# Bench.net
KiCad netlist of a schematic drawn in EAGLE
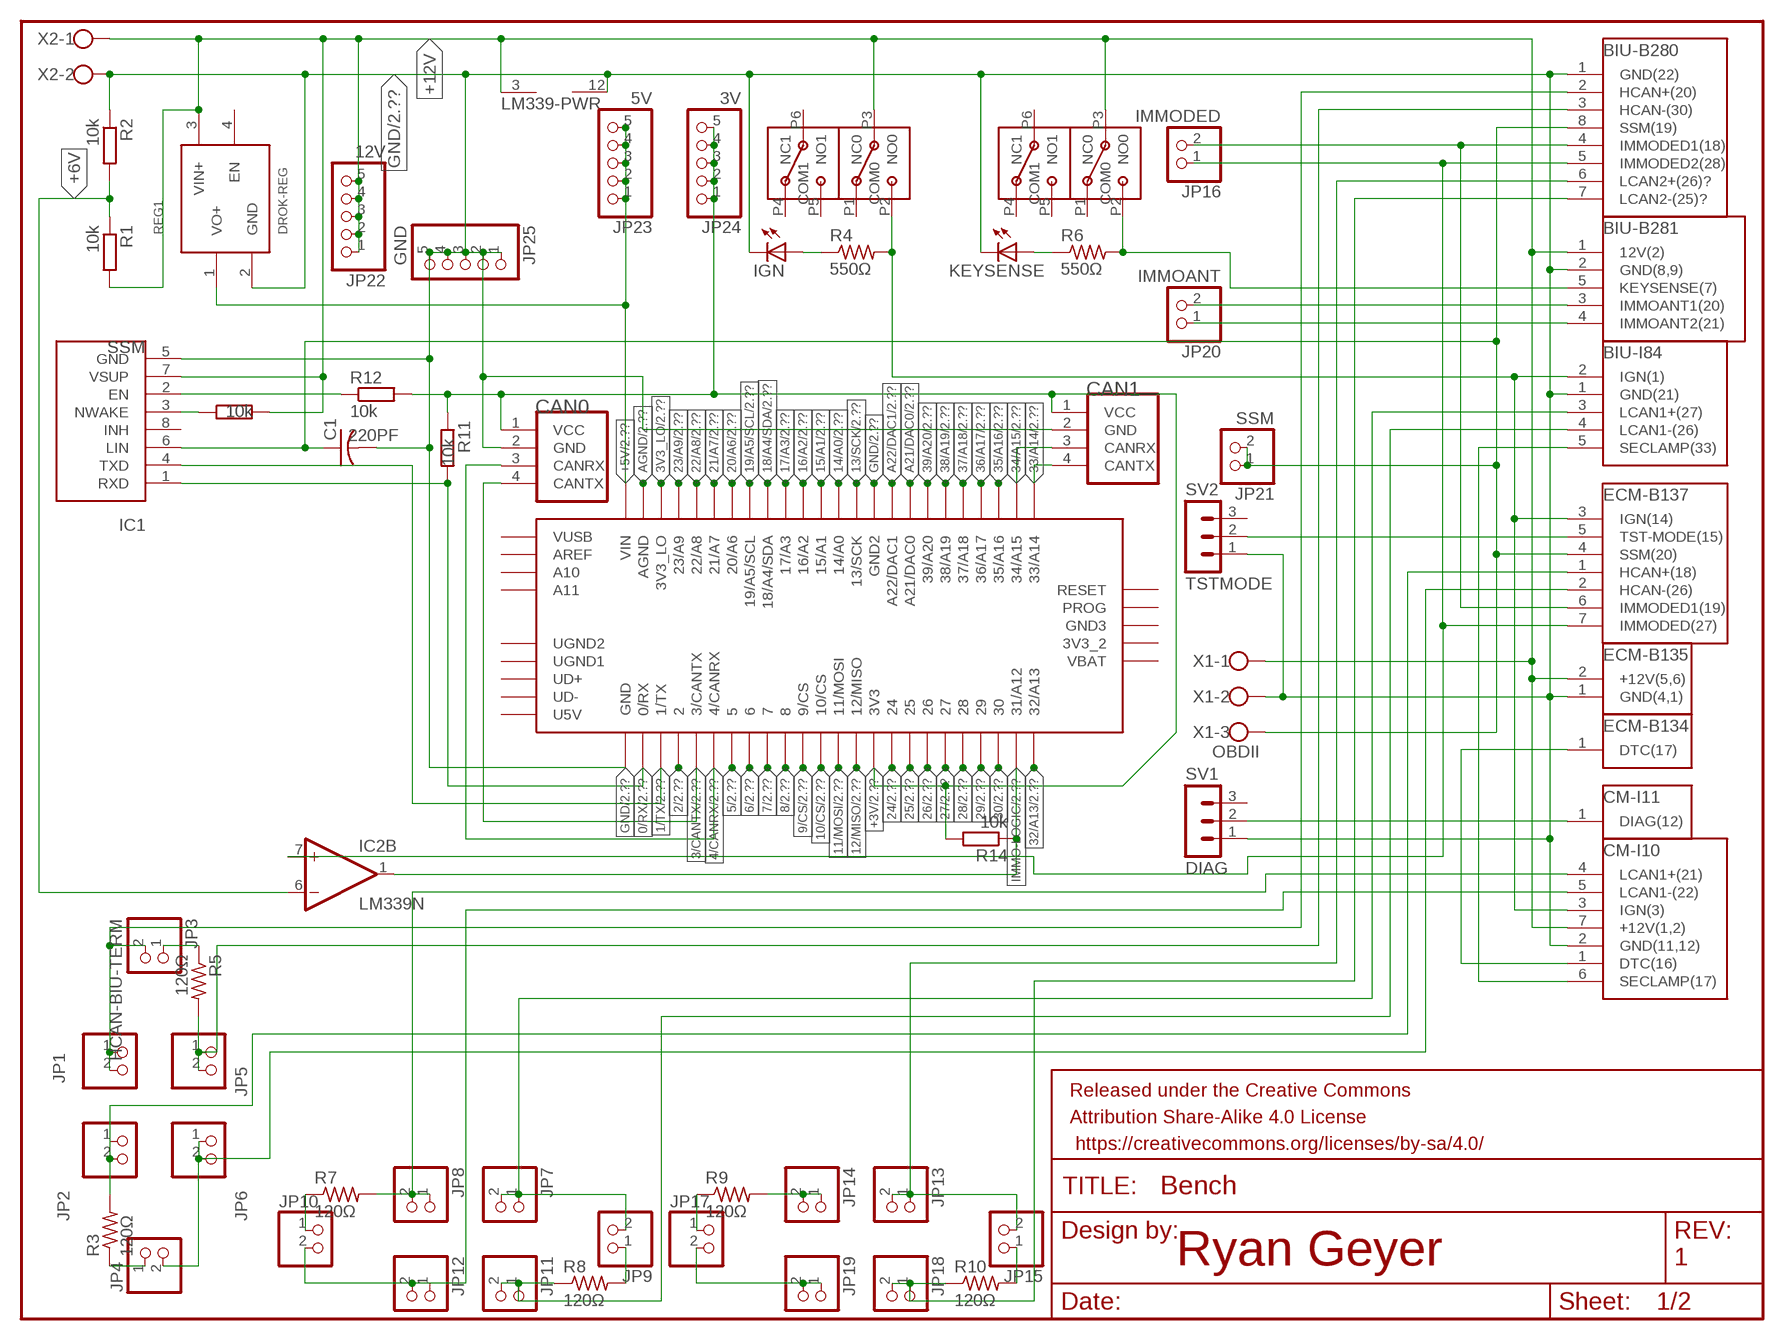
[diagram p0: schematic, sheet 1]
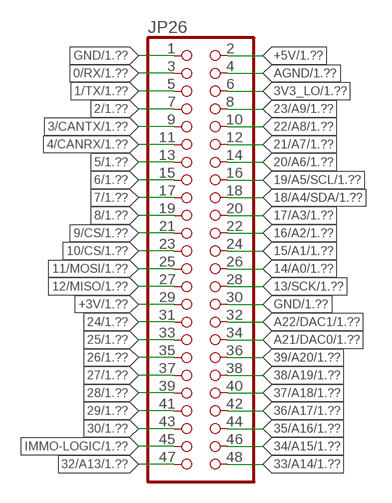
[diagram p1: schematic, sheet 2]

(export (version "E")
  (design (tool "Eeschema 10.0.6"))
  (components
    (comp (ref "C1")
      (value "220PF")
      (footprint "eagle-import:C050-024X044")
      (libsource (lib "eagle-import") (part "C-US050-024X044"))
    )
    (comp (ref "CAN0")
      (value "SN65HVD230D-BREAKOUT")
      (footprint "eagle-import:1X04")
      (libsource (lib "eagle-import") (part "SN65HVD230D-BREAKOUT"))
    )
    (comp (ref "CAN1")
      (value "SN65HVD230D-BREAKOUT")
      (footprint "eagle-import:1X04")
      (libsource (lib "eagle-import") (part "SN65HVD230D-BREAKOUT"))
    )
    (comp (ref "CONN1")
      (value "CM-110")
      (footprint "eagle-import:CM-110")
      (libsource (lib "eagle-import") (part "CM-110"))
    )
    (comp (ref "CONN2")
      (value "CM-I11")
      (footprint "eagle-import:ECM-B134")
      (libsource (lib "eagle-import") (part "CM-I11"))
    )
    (comp (ref "CONN3")
      (value "BIU-B280")
      (footprint "eagle-import:BIU-B280")
      (libsource (lib "eagle-import") (part "BIU-B280"))
    )
    (comp (ref "CONN4")
      (value "BIU-B281")
      (footprint "eagle-import:BIU-B281")
      (libsource (lib "eagle-import") (part "BIU-B281"))
    )
    (comp (ref "CONN5")
      (value "BIU-I84")
      (footprint "eagle-import:BIU-I84")
      (libsource (lib "eagle-import") (part "BIU-I84"))
    )
    (comp (ref "CONN6")
      (value "ECM-B135")
      (footprint "eagle-import:ECM-B135")
      (libsource (lib "eagle-import") (part "ECM-B135"))
    )
    (comp (ref "CONN7")
      (value "ECM-B137")
      (footprint "eagle-import:ECM-B137")
      (libsource (lib "eagle-import") (part "ECM-B137"))
    )
    (comp (ref "CONN8")
      (value "ECM-B134")
      (footprint "eagle-import:ECM-B134")
      (libsource (lib "eagle-import") (part "ECM-B134"))
    )
    (comp (ref "FRAME1")
      (value "FRAME-LETTER")
      (footprint "eagle-import:CREATIVE_COMMONS")
      (libsource (lib "eagle-import") (part "FRAME-LETTER"))
    )
    (comp (ref "IC1")
      (value "SSM")
      (footprint "eagle-import:DIL8")
      (libsource (lib "eagle-import") (part "SN65HDVA195-Q1DIL8"))
    )
    (comp (ref "IC2")
      (value "LM339N")
      (footprint "eagle-import:DIL14")
      (fields (field (name "SPICEPREFIX") "J"))
      (libsource (lib "eagle-import") (part "LM339N"))
    )
    (comp (ref "IGN")
      (value "LED3MM")
      (footprint "eagle-import:LED3MM")
      (libsource (lib "eagle-import") (part "LED3MM"))
    )
    (comp (ref "JP1")
      (value "PINHD-1X2")
      (footprint "eagle-import:1X02")
      (libsource (lib "eagle-import") (part "PINHD-1X2"))
    )
    (comp (ref "JP2")
      (value "PINHD-1X2")
      (footprint "eagle-import:1X02")
      (libsource (lib "eagle-import") (part "PINHD-1X2"))
    )
    (comp (ref "JP3")
      (value "HCAN-BIU-TERM")
      (footprint "eagle-import:1X02")
      (libsource (lib "eagle-import") (part "PINHD-1X2"))
    )
    (comp (ref "JP4")
      (value "PINHD-1X2")
      (footprint "eagle-import:1X02")
      (libsource (lib "eagle-import") (part "PINHD-1X2"))
    )
    (comp (ref "JP5")
      (value "PINHD-1X2")
      (footprint "eagle-import:1X02")
      (libsource (lib "eagle-import") (part "PINHD-1X2"))
    )
    (comp (ref "JP6")
      (value "PINHD-1X2")
      (footprint "eagle-import:1X02")
      (libsource (lib "eagle-import") (part "PINHD-1X2"))
    )
    (comp (ref "JP7")
      (value "PINHD-1X2")
      (footprint "eagle-import:1X02")
      (libsource (lib "eagle-import") (part "PINHD-1X2"))
    )
    (comp (ref "JP8")
      (value "PINHD-1X2")
      (footprint "eagle-import:1X02")
      (libsource (lib "eagle-import") (part "PINHD-1X2"))
    )
    (comp (ref "JP9")
      (value "PINHD-1X2")
      (footprint "eagle-import:1X02")
      (libsource (lib "eagle-import") (part "PINHD-1X2"))
    )
    (comp (ref "JP10")
      (value "PINHD-1X2")
      (footprint "eagle-import:1X02")
      (libsource (lib "eagle-import") (part "PINHD-1X2"))
    )
    (comp (ref "JP11")
      (value "PINHD-1X2")
      (footprint "eagle-import:1X02")
      (libsource (lib "eagle-import") (part "PINHD-1X2"))
    )
    (comp (ref "JP12")
      (value "PINHD-1X2")
      (footprint "eagle-import:1X02")
      (libsource (lib "eagle-import") (part "PINHD-1X2"))
    )
    (comp (ref "JP13")
      (value "PINHD-1X2")
      (footprint "eagle-import:1X02")
      (libsource (lib "eagle-import") (part "PINHD-1X2"))
    )
    (comp (ref "JP14")
      (value "PINHD-1X2")
      (footprint "eagle-import:1X02")
      (libsource (lib "eagle-import") (part "PINHD-1X2"))
    )
    (comp (ref "JP15")
      (value "PINHD-1X2")
      (footprint "eagle-import:1X02")
      (libsource (lib "eagle-import") (part "PINHD-1X2"))
    )
    (comp (ref "JP16")
      (value "IMMODED")
      (footprint "eagle-import:1X02")
      (libsource (lib "eagle-import") (part "PINHD-1X2"))
    )
    (comp (ref "JP17")
      (value "PINHD-1X2")
      (footprint "eagle-import:1X02")
      (libsource (lib "eagle-import") (part "PINHD-1X2"))
    )
    (comp (ref "JP18")
      (value "PINHD-1X2")
      (footprint "eagle-import:1X02")
      (libsource (lib "eagle-import") (part "PINHD-1X2"))
    )
    (comp (ref "JP19")
      (value "PINHD-1X2")
      (footprint "eagle-import:1X02")
      (libsource (lib "eagle-import") (part "PINHD-1X2"))
    )
    (comp (ref "JP20")
      (value "IMMOANT")
      (footprint "eagle-import:1X02")
      (libsource (lib "eagle-import") (part "PINHD-1X2"))
    )
    (comp (ref "JP21")
      (value "SSM")
      (footprint "eagle-import:1X02")
      (libsource (lib "eagle-import") (part "PINHD-1X2"))
    )
    (comp (ref "JP22")
      (value "12V")
      (footprint "eagle-import:1X05")
      (libsource (lib "eagle-import") (part "PINHD-1X5"))
    )
    (comp (ref "JP23")
      (value "5V")
      (footprint "eagle-import:1X05")
      (libsource (lib "eagle-import") (part "PINHD-1X5"))
    )
    (comp (ref "JP24")
      (value "3V")
      (footprint "eagle-import:1X05")
      (libsource (lib "eagle-import") (part "PINHD-1X5"))
    )
    (comp (ref "JP25")
      (value "GND")
      (footprint "eagle-import:1X05")
      (libsource (lib "eagle-import") (part "PINHD-1X5"))
    )
    (comp (ref "KEYSENSE")
      (value "LED3MM")
      (footprint "eagle-import:LED3MM")
      (libsource (lib "eagle-import") (part "LED3MM"))
    )
    (comp (ref "MCU1")
      (value "TEENSY_3.5/3.6")
      (footprint "eagle-import:TEENSY_3.5_3.6")
      (libsource (lib "eagle-import") (part "TEENSY_3.5/3.6"))
    )
    (comp (ref "R1")
      (value "10k")
      (footprint "eagle-import:0207_10")
      (libsource (lib "eagle-import") (part "R0207/10"))
    )
    (comp (ref "R2")
      (value "10k")
      (footprint "eagle-import:0207_10")
      (libsource (lib "eagle-import") (part "R0207/10"))
    )
    (comp (ref "R3")
      (value "120Ω")
      (footprint "eagle-import:0207_10")
      (libsource (lib "eagle-import") (part "R-US_0207/10"))
    )
    (comp (ref "R4")
      (value "550Ω")
      (footprint "eagle-import:0207_10")
      (libsource (lib "eagle-import") (part "R-US_0207/10"))
    )
    (comp (ref "R5")
      (value "120Ω")
      (footprint "eagle-import:0207_10")
      (libsource (lib "eagle-import") (part "R-US_0207/10"))
    )
    (comp (ref "R6")
      (value "550Ω")
      (footprint "eagle-import:0207_10")
      (libsource (lib "eagle-import") (part "R-US_0207/10"))
    )
    (comp (ref "R7")
      (value "120Ω")
      (footprint "eagle-import:0207_10")
      (libsource (lib "eagle-import") (part "R-US_0207/10"))
    )
    (comp (ref "R8")
      (value "120Ω")
      (footprint "eagle-import:0207_10")
      (libsource (lib "eagle-import") (part "R-US_0207/10"))
    )
    (comp (ref "R9")
      (value "120Ω")
      (footprint "eagle-import:0207_10")
      (libsource (lib "eagle-import") (part "R-US_0207/10"))
    )
    (comp (ref "R10")
      (value "120Ω")
      (footprint "eagle-import:0207_10")
      (libsource (lib "eagle-import") (part "R-US_0207/10"))
    )
    (comp (ref "R11")
      (value "10k")
      (footprint "eagle-import:0207_10")
      (libsource (lib "eagle-import") (part "R0207/10"))
    )
    (comp (ref "R12")
      (value "10k")
      (footprint "eagle-import:0207_10")
      (libsource (lib "eagle-import") (part "R0207/10"))
    )
    (comp (ref "R13")
      (value "10k")
      (footprint "eagle-import:0207_10")
      (libsource (lib "eagle-import") (part "R0207/10"))
    )
    (comp (ref "R14")
      (value "10k")
      (footprint "eagle-import:0207_10")
      (libsource (lib "eagle-import") (part "R0207/10"))
    )
    (comp (ref "REG1")
      (value "DROK-REG")
      (footprint "eagle-import:DROK-REG")
      (libsource (lib "eagle-import") (part "DROK-REG"))
    )
    (comp (ref "SV1")
      (value "DIAG")
      (footprint "eagle-import:MA03-1")
      (libsource (lib "eagle-import") (part "MA03-1"))
    )
    (comp (ref "SV2")
      (value "TSTMODE")
      (footprint "eagle-import:MA03-1")
      (libsource (lib "eagle-import") (part "MA03-1"))
    )
    (comp (ref "SW1")
      (value "8MM-DPDT")
      (footprint "eagle-import:8MM-DPDT")
      (libsource (lib "eagle-import") (part "8MM-DPDT"))
    )
    (comp (ref "SW2")
      (value "8MM-DPDT")
      (footprint "eagle-import:8MM-DPDT")
      (libsource (lib "eagle-import") (part "8MM-DPDT"))
    )
    (comp (ref "X1")
      (value "OBDII")
      (footprint "eagle-import:W237-103")
      (fields (field (name "MPN") "237-103"))
      (libsource (lib "eagle-import") (part "W237-103"))
    )
    (comp (ref "X2")
      (value "GND")
      (footprint "eagle-import:W237-102")
      (fields (field (name "MPN") "237-102"))
      (libsource (lib "eagle-import") (part "W237-102"))
    )
    (comp (ref "JP26")
      (value "PINHD-2X24")
      (footprint "eagle-import:2X24")
      (libsource (lib "eagle-import") (part "PINHD-2X24"))
    )
  )
  (nets
    (net (code "1") (name "+3V") (class "Default")
      (node (ref "CAN0") (pin "1") (pinfunction "VCC_1") (pintype "power_in"))
      (node (ref "CAN1") (pin "1") (pinfunction "VCC_1") (pintype "power_in"))
      (node (ref "JP24") (pin "1") (pinfunction "1_1") (pintype "passive"))
      (node (ref "JP24") (pin "2") (pinfunction "2_2") (pintype "passive"))
      (node (ref "JP24") (pin "3") (pinfunction "3_3") (pintype "passive"))
      (node (ref "JP24") (pin "4") (pinfunction "4_4") (pintype "passive"))
      (node (ref "JP24") (pin "5") (pinfunction "5_5") (pintype "passive"))
      (node (ref "JP26") (pin "29") (pinfunction "29_29") (pintype "passive"))
      (node (ref "MCU1") (pin "3V3") (pinfunction "3V3_3V3") (pintype "bidirectional"))
      (node (ref "R11") (pin "1") (pinfunction "1_1") (pintype "passive"))
      (node (ref "R12") (pin "2") (pinfunction "2_2") (pintype "passive"))
      (node (ref "R14") (pin "2") (pinfunction "2_2") (pintype "passive"))
    )
    (net (code "2") (name "+5V") (class "Default")
      (node (ref "JP23") (pin "1") (pinfunction "1_1") (pintype "passive"))
      (node (ref "JP23") (pin "2") (pinfunction "2_2") (pintype "passive"))
      (node (ref "JP23") (pin "3") (pinfunction "3_3") (pintype "passive"))
      (node (ref "JP23") (pin "4") (pinfunction "4_4") (pintype "passive"))
      (node (ref "JP23") (pin "5") (pinfunction "5_5") (pintype "passive"))
      (node (ref "JP26") (pin "2") (pinfunction "2_2") (pintype "passive"))
      (node (ref "MCU1") (pin "VIN") (pinfunction "VIN_VIN") (pintype "bidirectional"))
      (node (ref "REG1") (pin "1") (pinfunction "VO+_1") (pintype "output"))
    )
    (net (code "3") (name "+6V") (class "Default")
      (node (ref "IC2") (pin "6") (pinfunction "-IN_6") (pintype "input"))
      (node (ref "R1") (pin "1") (pinfunction "1_1") (pintype "passive"))
      (node (ref "R2") (pin "2") (pinfunction "2_2") (pintype "passive"))
    )
    (net (code "4") (name "+12V") (class "Default")
      (node (ref "CONN1") (pin "7") (pinfunction "+12V(1,2)_7") (pintype "bidirectional"))
      (node (ref "CONN4") (pin "1") (pinfunction "12V(2)_1") (pintype "bidirectional"))
      (node (ref "CONN6") (pin "2") (pinfunction "+12V(5,6)_2") (pintype "power_in"))
      (node (ref "IC1") (pin "7") (pinfunction "VSUP_7") (pintype "power_in"))
      (node (ref "IC2") (pin "3") (pinfunction "V+_3") (pintype "power_in"))
      (node (ref "JP22") (pin "1") (pinfunction "1_1") (pintype "passive"))
      (node (ref "JP22") (pin "2") (pinfunction "2_2") (pintype "passive"))
      (node (ref "JP22") (pin "3") (pinfunction "3_3") (pintype "passive"))
      (node (ref "JP22") (pin "4") (pinfunction "4_4") (pintype "passive"))
      (node (ref "JP22") (pin "5") (pinfunction "5_5") (pintype "passive"))
      (node (ref "R1") (pin "2") (pinfunction "2_2") (pintype "passive"))
      (node (ref "R13") (pin "2") (pinfunction "2_2") (pintype "passive"))
      (node (ref "REG1") (pin "3") (pinfunction "VIN+_3") (pintype "power_in"))
      (node (ref "SW1") (pin "P3") (pinfunction "COM0_P3") (pintype "bidirectional"))
      (node (ref "SW2") (pin "P3") (pinfunction "COM0_P3") (pintype "bidirectional"))
      (node (ref "X1") (pin "1") (pinfunction "KL_1") (pintype "passive"))
      (node (ref "X2") (pin "1") (pinfunction "KL_1") (pintype "passive"))
    )
    (net (code "5") (name "0{slash}RX") (class "Default")
      (node (ref "IC1") (pin "1") (pinfunction "RXD_1") (pintype "output"))
      (node (ref "JP26") (pin "3") (pinfunction "3_3") (pintype "passive"))
      (node (ref "MCU1") (pin "0/RX") (pinfunction "0/RX_0/RX") (pintype "bidirectional"))
      (node (ref "R11") (pin "2") (pinfunction "2_2") (pintype "passive"))
    )
    (net (code "6") (name "1{slash}TX") (class "Default")
      (node (ref "IC1") (pin "4") (pinfunction "TXD_4") (pintype "input"))
      (node (ref "JP26") (pin "5") (pinfunction "5_5") (pintype "passive"))
      (node (ref "MCU1") (pin "1/TX") (pinfunction "1/TX_1/TX") (pintype "bidirectional"))
    )
    (net (code "7") (name "2") (class "Default")
      (node (ref "JP26") (pin "7") (pinfunction "7_7") (pintype "passive"))
      (node (ref "MCU1") (pin "2") (pinfunction "2_2") (pintype "bidirectional"))
    )
    (net (code "8") (name "3V3_LO") (class "Default")
      (node (ref "JP26") (pin "6") (pinfunction "6_6") (pintype "passive"))
      (node (ref "MCU1") (pin "3V3_LO") (pinfunction "3V3_LO_3V3_LO") (pintype "bidirectional"))
    )
    (net (code "9") (name "3{slash}CANTX") (class "Default")
      (node (ref "CAN0") (pin "4") (pinfunction "CANTX_4") (pintype "input"))
      (node (ref "JP26") (pin "9") (pinfunction "9_9") (pintype "passive"))
      (node (ref "MCU1") (pin "3/CANTX") (pinfunction "3/CANTX_3/CANTX") (pintype "bidirectional"))
    )
    (net (code "10") (name "4{slash}CANRX") (class "Default")
      (node (ref "CAN0") (pin "3") (pinfunction "CANRX_3") (pintype "input"))
      (node (ref "JP26") (pin "11") (pinfunction "11_11") (pintype "passive"))
      (node (ref "MCU1") (pin "4/CANRX") (pinfunction "4/CANRX_4/CANRX") (pintype "bidirectional"))
    )
    (net (code "11") (name "5") (class "Default")
      (node (ref "JP26") (pin "13") (pinfunction "13_13") (pintype "passive"))
      (node (ref "MCU1") (pin "5") (pinfunction "5_5") (pintype "bidirectional"))
    )
    (net (code "12") (name "6") (class "Default")
      (node (ref "JP26") (pin "15") (pinfunction "15_15") (pintype "passive"))
      (node (ref "MCU1") (pin "6") (pinfunction "6_6") (pintype "bidirectional"))
    )
    (net (code "13") (name "7") (class "Default")
      (node (ref "JP26") (pin "17") (pinfunction "17_17") (pintype "passive"))
      (node (ref "MCU1") (pin "7") (pinfunction "7_7") (pintype "bidirectional"))
    )
    (net (code "14") (name "8") (class "Default")
      (node (ref "JP26") (pin "19") (pinfunction "19_19") (pintype "passive"))
      (node (ref "MCU1") (pin "8") (pinfunction "8_8") (pintype "bidirectional"))
    )
    (net (code "15") (name "9{slash}CS") (class "Default")
      (node (ref "JP26") (pin "21") (pinfunction "21_21") (pintype "passive"))
      (node (ref "MCU1") (pin "9/CS") (pinfunction "9/CS_9/CS") (pintype "bidirectional"))
    )
    (net (code "16") (name "10{slash}CS") (class "Default")
      (node (ref "JP26") (pin "23") (pinfunction "23_23") (pintype "passive"))
      (node (ref "MCU1") (pin "10/CS") (pinfunction "10/CS_10/CS") (pintype "bidirectional"))
    )
    (net (code "17") (name "11{slash}MOSI") (class "Default")
      (node (ref "JP26") (pin "25") (pinfunction "25_25") (pintype "passive"))
      (node (ref "MCU1") (pin "11/MOSI") (pinfunction "11/MOSI_11/MOSI") (pintype "bidirectional"))
    )
    (net (code "18") (name "12{slash}MISO") (class "Default")
      (node (ref "JP26") (pin "27") (pinfunction "27_27") (pintype "passive"))
      (node (ref "MCU1") (pin "12/MISO") (pinfunction "12/MISO_12/MISO") (pintype "bidirectional"))
    )
    (net (code "19") (name "13{slash}SCK") (class "Default")
      (node (ref "JP26") (pin "28") (pinfunction "28_28") (pintype "passive"))
      (node (ref "MCU1") (pin "13/SCK") (pinfunction "13/SCK_13/SCK") (pintype "bidirectional"))
    )
    (net (code "20") (name "14{slash}A0") (class "Default")
      (node (ref "JP26") (pin "26") (pinfunction "26_26") (pintype "passive"))
      (node (ref "MCU1") (pin "14/A0") (pinfunction "14/A0_14/A0") (pintype "bidirectional"))
    )
    (net (code "21") (name "15{slash}A1") (class "Default")
      (node (ref "JP26") (pin "24") (pinfunction "24_24") (pintype "passive"))
      (node (ref "MCU1") (pin "15/A1") (pinfunction "15/A1_15/A1") (pintype "bidirectional"))
    )
    (net (code "22") (name "16{slash}A2") (class "Default")
      (node (ref "JP26") (pin "22") (pinfunction "22_22") (pintype "passive"))
      (node (ref "MCU1") (pin "16/A2") (pinfunction "16/A2_16/A2") (pintype "bidirectional"))
    )
    (net (code "23") (name "17{slash}A3") (class "Default")
      (node (ref "JP26") (pin "20") (pinfunction "20_20") (pintype "passive"))
      (node (ref "MCU1") (pin "17/A3") (pinfunction "17/A3_17/A3") (pintype "bidirectional"))
    )
    (net (code "24") (name "18{slash}A4{slash}SDA") (class "Default")
      (node (ref "JP26") (pin "18") (pinfunction "18_18") (pintype "passive"))
      (node (ref "MCU1") (pin "18/A4/SDA") (pinfunction "18/A4/SDA_18/A4/SDA") (pintype "bidirectional"))
    )
    (net (code "25") (name "19{slash}A5{slash}SCL") (class "Default")
      (node (ref "JP26") (pin "16") (pinfunction "16_16") (pintype "passive"))
      (node (ref "MCU1") (pin "19/A5/SCL") (pinfunction "19/A5/SCL_19/A5/SCL") (pintype "bidirectional"))
    )
    (net (code "26") (name "20{slash}A6") (class "Default")
      (node (ref "JP26") (pin "14") (pinfunction "14_14") (pintype "passive"))
      (node (ref "MCU1") (pin "20/A6") (pinfunction "20/A6_20/A6") (pintype "bidirectional"))
    )
    (net (code "27") (name "21{slash}A7") (class "Default")
      (node (ref "JP26") (pin "12") (pinfunction "12_12") (pintype "passive"))
      (node (ref "MCU1") (pin "21/A7") (pinfunction "21/A7_21/A7") (pintype "bidirectional"))
    )
    (net (code "28") (name "22{slash}A8") (class "Default")
      (node (ref "JP26") (pin "10") (pinfunction "10_10") (pintype "passive"))
      (node (ref "MCU1") (pin "22/A8") (pinfunction "22/A8_22/A8") (pintype "bidirectional"))
    )
    (net (code "29") (name "23{slash}A9") (class "Default")
      (node (ref "JP26") (pin "8") (pinfunction "8_8") (pintype "passive"))
      (node (ref "MCU1") (pin "23/A9") (pinfunction "23/A9_23/A9") (pintype "bidirectional"))
    )
    (net (code "30") (name "24") (class "Default")
      (node (ref "JP26") (pin "31") (pinfunction "31_31") (pintype "passive"))
      (node (ref "MCU1") (pin "24") (pinfunction "24_24") (pintype "bidirectional"))
    )
    (net (code "31") (name "25") (class "Default")
      (node (ref "JP26") (pin "33") (pinfunction "33_33") (pintype "passive"))
      (node (ref "MCU1") (pin "25") (pinfunction "25_25") (pintype "bidirectional"))
    )
    (net (code "32") (name "26") (class "Default")
      (node (ref "JP26") (pin "35") (pinfunction "35_35") (pintype "passive"))
      (node (ref "MCU1") (pin "26") (pinfunction "26_26") (pintype "bidirectional"))
    )
    (net (code "33") (name "27") (class "Default")
      (node (ref "JP26") (pin "37") (pinfunction "37_37") (pintype "passive"))
      (node (ref "MCU1") (pin "27") (pinfunction "27_27") (pintype "bidirectional"))
    )
    (net (code "34") (name "28") (class "Default")
      (node (ref "JP26") (pin "39") (pinfunction "39_39") (pintype "passive"))
      (node (ref "MCU1") (pin "28") (pinfunction "28_28") (pintype "bidirectional"))
    )
    (net (code "35") (name "29") (class "Default")
      (node (ref "JP26") (pin "41") (pinfunction "41_41") (pintype "passive"))
      (node (ref "MCU1") (pin "29") (pinfunction "29_29") (pintype "bidirectional"))
    )
    (net (code "36") (name "30") (class "Default")
      (node (ref "JP26") (pin "43") (pinfunction "43_43") (pintype "passive"))
      (node (ref "MCU1") (pin "30") (pinfunction "30_30") (pintype "bidirectional"))
    )
    (net (code "37") (name "32{slash}A13") (class "Default")
      (node (ref "JP26") (pin "47") (pinfunction "47_47") (pintype "passive"))
      (node (ref "MCU1") (pin "32/A13") (pinfunction "32/A13_32/A13") (pintype "bidirectional"))
    )
    (net (code "38") (name "33{slash}A14") (class "Default")
      (node (ref "CAN1") (pin "4") (pinfunction "CANTX_4") (pintype "input"))
      (node (ref "JP26") (pin "48") (pinfunction "48_48") (pintype "passive"))
      (node (ref "MCU1") (pin "33/A14") (pinfunction "33/A14_33/A14") (pintype "bidirectional"))
    )
    (net (code "39") (name "34{slash}A15") (class "Default")
      (node (ref "CAN1") (pin "3") (pinfunction "CANRX_3") (pintype "input"))
      (node (ref "JP26") (pin "46") (pinfunction "46_46") (pintype "passive"))
      (node (ref "MCU1") (pin "34/A15") (pinfunction "34/A15_34/A15") (pintype "bidirectional"))
    )
    (net (code "40") (name "35{slash}A16") (class "Default")
      (node (ref "JP26") (pin "44") (pinfunction "44_44") (pintype "passive"))
      (node (ref "MCU1") (pin "35/A16") (pinfunction "35/A16_35/A16") (pintype "bidirectional"))
    )
    (net (code "41") (name "36{slash}A17") (class "Default")
      (node (ref "JP26") (pin "42") (pinfunction "42_42") (pintype "passive"))
      (node (ref "MCU1") (pin "36/A17") (pinfunction "36/A17_36/A17") (pintype "bidirectional"))
    )
    (net (code "42") (name "37{slash}A18") (class "Default")
      (node (ref "JP26") (pin "40") (pinfunction "40_40") (pintype "passive"))
      (node (ref "MCU1") (pin "37/A18") (pinfunction "37/A18_37/A18") (pintype "bidirectional"))
    )
    (net (code "43") (name "38{slash}A19") (class "Default")
      (node (ref "JP26") (pin "38") (pinfunction "38_38") (pintype "passive"))
      (node (ref "MCU1") (pin "38/A19") (pinfunction "38/A19_38/A19") (pintype "bidirectional"))
    )
    (net (code "44") (name "39{slash}A20") (class "Default")
      (node (ref "JP26") (pin "36") (pinfunction "36_36") (pintype "passive"))
      (node (ref "MCU1") (pin "39/A20") (pinfunction "39/A20_39/A20") (pintype "bidirectional"))
    )
    (net (code "45") (name "A21{slash}DAC0") (class "Default")
      (node (ref "JP26") (pin "34") (pinfunction "34_34") (pintype "passive"))
      (node (ref "MCU1") (pin "21/DAC0") (pinfunction "A21/DAC0_21/DAC0") (pintype "bidirectional"))
    )
    (net (code "46") (name "A22{slash}DAC1") (class "Default")
      (node (ref "JP26") (pin "32") (pinfunction "32_32") (pintype "passive"))
      (node (ref "MCU1") (pin "A22/DAC1") (pinfunction "A22/DAC1_A22/DAC1") (pintype "bidirectional"))
    )
    (net (code "47") (name "AGND") (class "Default")
      (node (ref "JP26") (pin "4") (pinfunction "4_4") (pintype "passive"))
      (node (ref "MCU1") (pin "AGND") (pinfunction "AGND_AGND") (pintype "bidirectional"))
    )
    (net (code "48") (name "GND") (class "Default")
      (node (ref "C1") (pin "2") (pinfunction "2_2") (pintype "passive"))
      (node (ref "CAN0") (pin "2") (pinfunction "GND_2") (pintype "passive"))
      (node (ref "CAN1") (pin "2") (pinfunction "GND_2") (pintype "passive"))
      (node (ref "CONN1") (pin "2") (pinfunction "GND(11,12)_2") (pintype "bidirectional"))
      (node (ref "CONN3") (pin "1") (pinfunction "GND(22)_1") (pintype "power_in"))
      (node (ref "CONN4") (pin "2") (pinfunction "GND(8,9)_2") (pintype "bidirectional"))
      (node (ref "CONN5") (pin "1") (pinfunction "GND(21)_1") (pintype "power_in"))
      (node (ref "CONN6") (pin "1") (pinfunction "GND(4,1)_1") (pintype "power_in"))
      (node (ref "IC1") (pin "5") (pinfunction "GND_5") (pintype "power_in"))
      (node (ref "IC2") (pin "12") (pinfunction "GND_12") (pintype "power_in"))
      (node (ref "IGN") (pin "K") (pinfunction "C_K") (pintype "passive"))
      (node (ref "JP25") (pin "1") (pinfunction "1_1") (pintype "passive"))
      (node (ref "JP25") (pin "2") (pinfunction "2_2") (pintype "passive"))
      (node (ref "JP25") (pin "3") (pinfunction "3_3") (pintype "passive"))
      (node (ref "JP25") (pin "4") (pinfunction "4_4") (pintype "passive"))
      (node (ref "JP25") (pin "5") (pinfunction "5_5") (pintype "passive"))
      (node (ref "JP26") (pin "1") (pinfunction "1_1") (pintype "passive"))
      (node (ref "JP26") (pin "30") (pinfunction "30_30") (pintype "passive"))
      (node (ref "KEYSENSE") (pin "K") (pinfunction "C_K") (pintype "passive"))
      (node (ref "MCU1") (pin "GND") (pinfunction "GND_GND") (pintype "bidirectional"))
      (node (ref "MCU1") (pin "GND2") (pinfunction "GND2_GND2") (pintype "bidirectional"))
      (node (ref "R2") (pin "1") (pinfunction "1_1") (pintype "passive"))
      (node (ref "REG1") (pin "2") (pinfunction "GND_2") (pintype "power_in"))
      (node (ref "SV1") (pin "1") (pinfunction "1_1") (pintype "passive"))
      (node (ref "SV2") (pin "1") (pinfunction "1_1") (pintype "passive"))
      (node (ref "X1") (pin "2") (pinfunction "KL_2") (pintype "passive"))
      (node (ref "X2") (pin "2") (pinfunction "KL_2") (pintype "passive"))
    )
    (net (code "49") (name "IMMO-LOGIC") (class "Default")
      (node (ref "IC2") (pin "1") (pinfunction "OUT_1") (pintype "open_collector"))
      (node (ref "JP26") (pin "45") (pinfunction "45_45") (pintype "passive"))
      (node (ref "MCU1") (pin "31/A12") (pinfunction "31/A12_31/A12") (pintype "bidirectional"))
      (node (ref "R14") (pin "1") (pinfunction "1_1") (pintype "passive"))
    )
    (net (code "50") (name "Net-(CONN1-DTC(16))") (class "Default")
      (node (ref "CONN1") (pin "1") (pinfunction "DTC(16)_1") (pintype "bidirectional"))
      (node (ref "CONN8") (pin "1") (pinfunction "DTC(17)_1") (pintype "output"))
    )
    (net (code "51") (name "Net-(CONN1-IGN(3))") (class "Default")
      (node (ref "CONN1") (pin "3") (pinfunction "IGN(3)_3") (pintype "bidirectional"))
      (node (ref "CONN5") (pin "2") (pinfunction "IGN(1)_2") (pintype "input"))
      (node (ref "CONN7") (pin "3") (pinfunction "IGN(14)_3") (pintype "bidirectional"))
      (node (ref "R4") (pin "2") (pinfunction "2_2") (pintype "passive"))
      (node (ref "SW1") (pin "P2") (pinfunction "NO0_P2") (pintype "bidirectional"))
    )
    (net (code "52") (name "Net-(CONN1-LCAN1+(21))") (class "Default")
      (node (ref "CONN1") (pin "4") (pinfunction "LCAN1+(21)_4") (pintype "bidirectional"))
      (node (ref "JP8") (pin "1") (pinfunction "1_1") (pintype "passive"))
      (node (ref "JP8") (pin "2") (pinfunction "2_2") (pintype "passive"))
      (node (ref "R7") (pin "2") (pinfunction "2_2") (pintype "passive"))
    )
    (net (code "53") (name "Net-(CONN1-LCAN1-(22))") (class "Default")
      (node (ref "CONN1") (pin "5") (pinfunction "LCAN1-(22)_5") (pintype "bidirectional"))
      (node (ref "JP10") (pin "2") (pinfunction "2_2") (pintype "passive"))
      (node (ref "JP12") (pin "1") (pinfunction "1_1") (pintype "passive"))
      (node (ref "JP12") (pin "2") (pinfunction "2_2") (pintype "passive"))
    )
    (net (code "54") (name "Net-(CONN1-SECLAMP(17))") (class "Default")
      (node (ref "CONN1") (pin "6") (pinfunction "SECLAMP(17)_6") (pintype "bidirectional"))
      (node (ref "CONN5") (pin "5") (pinfunction "SECLAMP(33)_5") (pintype "bidirectional"))
    )
    (net (code "55") (name "Net-(CONN2-DIAG(12))") (class "Default")
      (node (ref "CONN2") (pin "1") (pinfunction "DIAG(12)_1") (pintype "bidirectional"))
      (node (ref "SV1") (pin "2") (pinfunction "2_2") (pintype "passive"))
    )
    (net (code "56") (name "Net-(CONN3-HCAN+(20))") (class "Default")
      (node (ref "CONN3") (pin "2") (pinfunction "HCAN+(20)_2") (pintype "bidirectional"))
      (node (ref "JP1") (pin "1") (pinfunction "1_1") (pintype "passive"))
      (node (ref "JP1") (pin "2") (pinfunction "2_2") (pintype "passive"))
      (node (ref "JP3") (pin "2") (pinfunction "2_2") (pintype "passive"))
    )
    (net (code "57") (name "Net-(CONN3-HCAN-(30))") (class "Default")
      (node (ref "CONN3") (pin "3") (pinfunction "HCAN-(30)_3") (pintype "bidirectional"))
      (node (ref "JP5") (pin "1") (pinfunction "1_1") (pintype "passive"))
      (node (ref "JP5") (pin "2") (pinfunction "2_2") (pintype "passive"))
      (node (ref "R5") (pin "2") (pinfunction "2_2") (pintype "passive"))
    )
    (net (code "58") (name "Net-(CONN3-IMMODED1(18))") (class "Default")
      (node (ref "CONN3") (pin "4") (pinfunction "IMMODED1(18)_4") (pintype "bidirectional"))
      (node (ref "CONN7") (pin "6") (pinfunction "IMMODED1(19)_6") (pintype "bidirectional"))
      (node (ref "JP16") (pin "2") (pinfunction "2_2") (pintype "passive"))
    )
    (net (code "59") (name "Net-(CONN3-IMMODED2(28))") (class "Default")
      (node (ref "CONN3") (pin "5") (pinfunction "IMMODED2(28)_5") (pintype "bidirectional"))
      (node (ref "CONN7") (pin "7") (pinfunction "IMMODED(27)_7") (pintype "bidirectional"))
      (node (ref "IC2") (pin "7") (pinfunction "+IN_7") (pintype "input"))
      (node (ref "JP16") (pin "1") (pinfunction "1_1") (pintype "passive"))
    )
    (net (code "60") (name "Net-(CONN3-LCAN2+(26)?)") (class "Default")
      (node (ref "CONN3") (pin "6") (pinfunction "LCAN2+(26)?_6") (pintype "bidirectional"))
      (node (ref "JP13") (pin "1") (pinfunction "1_1") (pintype "passive"))
      (node (ref "JP13") (pin "2") (pinfunction "2_2") (pintype "passive"))
      (node (ref "JP15") (pin "2") (pinfunction "2_2") (pintype "passive"))
    )
    (net (code "61") (name "Net-(CONN3-LCAN2-(25)?)") (class "Default")
      (node (ref "CONN3") (pin "7") (pinfunction "LCAN2-(25)?_7") (pintype "bidirectional"))
      (node (ref "JP18") (pin "1") (pinfunction "1_1") (pintype "passive"))
      (node (ref "JP18") (pin "2") (pinfunction "2_2") (pintype "passive"))
      (node (ref "R10") (pin "1") (pinfunction "1_1") (pintype "passive"))
    )
    (net (code "62") (name "Net-(CONN3-SSM(19))") (class "Default")
      (node (ref "C1") (pin "1") (pinfunction "1_1") (pintype "passive"))
      (node (ref "CONN3") (pin "8") (pinfunction "SSM(19)_8") (pintype "bidirectional"))
      (node (ref "CONN7") (pin "4") (pinfunction "SSM(20)_4") (pintype "bidirectional"))
      (node (ref "IC1") (pin "6") (pinfunction "LIN_6") (pintype "bidirectional"))
      (node (ref "JP21") (pin "1") (pinfunction "1_1") (pintype "passive"))
      (node (ref "JP21") (pin "2") (pinfunction "2_2") (pintype "passive"))
      (node (ref "X1") (pin "3") (pinfunction "KL_3") (pintype "passive"))
    )
    (net (code "63") (name "Net-(CONN4-IMMOANT1(20))") (class "Default")
      (node (ref "CONN4") (pin "3") (pinfunction "IMMOANT1(20)_3") (pintype "bidirectional"))
      (node (ref "JP20") (pin "2") (pinfunction "2_2") (pintype "passive"))
    )
    (net (code "64") (name "Net-(CONN4-IMMOANT2(21))") (class "Default")
      (node (ref "CONN4") (pin "4") (pinfunction "IMMOANT2(21)_4") (pintype "bidirectional"))
      (node (ref "JP20") (pin "1") (pinfunction "1_1") (pintype "passive"))
    )
    (net (code "65") (name "Net-(CONN4-KEYSENSE(7))") (class "Default")
      (node (ref "CONN4") (pin "5") (pinfunction "KEYSENSE(7)_5") (pintype "bidirectional"))
      (node (ref "R6") (pin "2") (pinfunction "2_2") (pintype "passive"))
      (node (ref "SW2") (pin "P2") (pinfunction "NO0_P2") (pintype "bidirectional"))
    )
    (net (code "66") (name "Net-(CONN5-LCAN1+(27))") (class "Default")
      (node (ref "CONN5") (pin "3") (pinfunction "LCAN1+(27)_3") (pintype "bidirectional"))
      (node (ref "JP7") (pin "1") (pinfunction "1_1") (pintype "passive"))
      (node (ref "JP7") (pin "2") (pinfunction "2_2") (pintype "passive"))
      (node (ref "JP9") (pin "2") (pinfunction "2_2") (pintype "passive"))
    )
    (net (code "67") (name "Net-(CONN5-LCAN1-(26))") (class "Default")
      (node (ref "CONN5") (pin "4") (pinfunction "LCAN1-(26)_4") (pintype "bidirectional"))
      (node (ref "JP11") (pin "1") (pinfunction "1_1") (pintype "passive"))
      (node (ref "JP11") (pin "2") (pinfunction "2_2") (pintype "passive"))
      (node (ref "R8") (pin "1") (pinfunction "1_1") (pintype "passive"))
    )
    (net (code "68") (name "Net-(CONN7-HCAN+(18))") (class "Default")
      (node (ref "CONN7") (pin "1") (pinfunction "HCAN+(18)_1") (pintype "bidirectional"))
      (node (ref "JP2") (pin "1") (pinfunction "1_1") (pintype "passive"))
      (node (ref "JP2") (pin "2") (pinfunction "2_2") (pintype "passive"))
      (node (ref "R3") (pin "2") (pinfunction "2_2") (pintype "passive"))
    )
    (net (code "69") (name "Net-(CONN7-HCAN-(26))") (class "Default")
      (node (ref "CONN7") (pin "2") (pinfunction "HCAN-(26)_2") (pintype "bidirectional"))
      (node (ref "JP4") (pin "2") (pinfunction "2_2") (pintype "passive"))
      (node (ref "JP6") (pin "1") (pinfunction "1_1") (pintype "passive"))
      (node (ref "JP6") (pin "2") (pinfunction "2_2") (pintype "passive"))
    )
    (net (code "70") (name "Net-(CONN7-TST-MODE(15))") (class "Default")
      (node (ref "CONN7") (pin "5") (pinfunction "TST-MODE(15)_5") (pintype "bidirectional"))
      (node (ref "SV2") (pin "2") (pinfunction "2_2") (pintype "passive"))
    )
    (net (code "71") (name "Net-(IC1-EN)") (class "Default")
      (node (ref "IC1") (pin "2") (pinfunction "EN_2") (pintype "input"))
      (node (ref "R12") (pin "1") (pinfunction "1_1") (pintype "passive"))
    )
    (net (code "72") (name "Net-(IC1-NWAKE)") (class "Default")
      (node (ref "IC1") (pin "3") (pinfunction "NWAKE_3") (pintype "input"))
      (node (ref "R13") (pin "1") (pinfunction "1_1") (pintype "passive"))
    )
    (net (code "73") (name "Net-(IGN-PadA)") (class "Default")
      (node (ref "IGN") (pin "A") (pinfunction "A_A") (pintype "passive"))
      (node (ref "R4") (pin "1") (pinfunction "1_1") (pintype "passive"))
    )
    (net (code "74") (name "Net-(JP3-Pad1)") (class "Default")
      (node (ref "JP3") (pin "1") (pinfunction "1_1") (pintype "passive"))
      (node (ref "R5") (pin "1") (pinfunction "1_1") (pintype "passive"))
    )
    (net (code "75") (name "Net-(JP4-Pad1)") (class "Default")
      (node (ref "JP4") (pin "1") (pinfunction "1_1") (pintype "passive"))
      (node (ref "R3") (pin "1") (pinfunction "1_1") (pintype "passive"))
    )
    (net (code "76") (name "Net-(JP9-Pad1)") (class "Default")
      (node (ref "JP9") (pin "1") (pinfunction "1_1") (pintype "passive"))
      (node (ref "R8") (pin "2") (pinfunction "2_2") (pintype "passive"))
    )
    (net (code "77") (name "Net-(JP10-Pad1)") (class "Default")
      (node (ref "JP10") (pin "1") (pinfunction "1_1") (pintype "passive"))
      (node (ref "R7") (pin "1") (pinfunction "1_1") (pintype "passive"))
    )
    (net (code "78") (name "Net-(JP14-Pad1)") (class "Default")
      (node (ref "JP14") (pin "1") (pinfunction "1_1") (pintype "passive"))
      (node (ref "JP14") (pin "2") (pinfunction "2_2") (pintype "passive"))
      (node (ref "R9") (pin "2") (pinfunction "2_2") (pintype "passive"))
    )
    (net (code "79") (name "Net-(JP15-Pad1)") (class "Default")
      (node (ref "JP15") (pin "1") (pinfunction "1_1") (pintype "passive"))
      (node (ref "R10") (pin "2") (pinfunction "2_2") (pintype "passive"))
    )
    (net (code "80") (name "Net-(JP17-Pad1)") (class "Default")
      (node (ref "JP17") (pin "1") (pinfunction "1_1") (pintype "passive"))
      (node (ref "R9") (pin "1") (pinfunction "1_1") (pintype "passive"))
    )
    (net (code "81") (name "Net-(JP17-Pad2)") (class "Default")
      (node (ref "JP17") (pin "2") (pinfunction "2_2") (pintype "passive"))
      (node (ref "JP19") (pin "1") (pinfunction "1_1") (pintype "passive"))
      (node (ref "JP19") (pin "2") (pinfunction "2_2") (pintype "passive"))
    )
    (net (code "82") (name "Net-(KEYSENSE-PadA)") (class "Default")
      (node (ref "KEYSENSE") (pin "A") (pinfunction "A_A") (pintype "passive"))
      (node (ref "R6") (pin "1") (pinfunction "1_1") (pintype "passive"))
    )
    (net (code "83") (name "unconnected-(IC1-INH-Pad8)") (class "Default")
      (node (ref "IC1") (pin "8") (pinfunction "INH_8") (pintype "output"))
    )
    (net (code "84") (name "unconnected-(MCU1-Pad3V3_2)") (class "Default")
      (node (ref "MCU1") (pin "3V3_2") (pinfunction "3V3_2_3V3_2") (pintype "bidirectional"))
    )
    (net (code "85") (name "unconnected-(MCU1-PadA10)") (class "Default")
      (node (ref "MCU1") (pin "A10") (pinfunction "A10_A10") (pintype "bidirectional"))
    )
    (net (code "86") (name "unconnected-(MCU1-PadA11)") (class "Default")
      (node (ref "MCU1") (pin "A11") (pinfunction "A11_A11") (pintype "bidirectional"))
    )
    (net (code "87") (name "unconnected-(MCU1-PadAREF)") (class "Default")
      (node (ref "MCU1") (pin "AREF") (pinfunction "AREF_AREF") (pintype "bidirectional"))
    )
    (net (code "88") (name "unconnected-(MCU1-PadGND3)") (class "Default")
      (node (ref "MCU1") (pin "GND3") (pinfunction "GND3_GND3") (pintype "bidirectional"))
    )
    (net (code "89") (name "unconnected-(MCU1-PadPROG)") (class "Default")
      (node (ref "MCU1") (pin "PROG") (pinfunction "PROG_PROG") (pintype "bidirectional"))
    )
    (net (code "90") (name "unconnected-(MCU1-PadRESET)") (class "Default")
      (node (ref "MCU1") (pin "RESET") (pinfunction "RESET_RESET") (pintype "bidirectional"))
    )
    (net (code "91") (name "unconnected-(MCU1-PadU5V)") (class "Default")
      (node (ref "MCU1") (pin "U5V") (pinfunction "U5V_U5V") (pintype "bidirectional"))
    )
    (net (code "92") (name "unconnected-(MCU1-PadUD+)") (class "Default")
      (node (ref "MCU1") (pin "UD+") (pinfunction "UD+_UD+") (pintype "bidirectional"))
    )
    (net (code "93") (name "unconnected-(MCU1-PadUD-)") (class "Default")
      (node (ref "MCU1") (pin "UD-") (pinfunction "UD-_UD-") (pintype "bidirectional"))
    )
    (net (code "94") (name "unconnected-(MCU1-PadUGND1)") (class "Default")
      (node (ref "MCU1") (pin "UGND1") (pinfunction "UGND1_UGND1") (pintype "bidirectional"))
    )
    (net (code "95") (name "unconnected-(MCU1-PadUGND2)") (class "Default")
      (node (ref "MCU1") (pin "UGND2") (pinfunction "UGND2_UGND2") (pintype "bidirectional"))
    )
    (net (code "96") (name "unconnected-(MCU1-PadVBAT)") (class "Default")
      (node (ref "MCU1") (pin "VBAT") (pinfunction "VBAT_VBAT") (pintype "bidirectional"))
    )
    (net (code "97") (name "unconnected-(MCU1-PadVUSB)") (class "Default")
      (node (ref "MCU1") (pin "VUSB") (pinfunction "VUSB_VUSB") (pintype "bidirectional"))
    )
    (net (code "98") (name "unconnected-(REG1-EN-Pad4)") (class "Default")
      (node (ref "REG1") (pin "4") (pinfunction "EN_4") (pintype "input"))
    )
    (net (code "99") (name "unconnected-(SV1-Pad3)") (class "Default")
      (node (ref "SV1") (pin "3") (pinfunction "3_3") (pintype "passive"))
    )
    (net (code "100") (name "unconnected-(SV2-Pad3)") (class "Default")
      (node (ref "SV2") (pin "3") (pinfunction "3_3") (pintype "passive"))
    )
    (net (code "101") (name "unconnected-(SW1-COM1-PadP6)") (class "Default")
      (node (ref "SW1") (pin "P6") (pinfunction "COM1_P6") (pintype "bidirectional"))
    )
    (net (code "102") (name "unconnected-(SW1-NC0-PadP1)") (class "Default")
      (node (ref "SW1") (pin "P1") (pinfunction "NC0_P1") (pintype "bidirectional"))
    )
    (net (code "103") (name "unconnected-(SW1-NC1-PadP4)") (class "Default")
      (node (ref "SW1") (pin "P4") (pinfunction "NC1_P4") (pintype "bidirectional"))
    )
    (net (code "104") (name "unconnected-(SW1-NO1-PadP5)") (class "Default")
      (node (ref "SW1") (pin "P5") (pinfunction "NO1_P5") (pintype "bidirectional"))
    )
    (net (code "105") (name "unconnected-(SW2-COM1-PadP6)") (class "Default")
      (node (ref "SW2") (pin "P6") (pinfunction "COM1_P6") (pintype "bidirectional"))
    )
    (net (code "106") (name "unconnected-(SW2-NC0-PadP1)") (class "Default")
      (node (ref "SW2") (pin "P1") (pinfunction "NC0_P1") (pintype "bidirectional"))
    )
    (net (code "107") (name "unconnected-(SW2-NC1-PadP4)") (class "Default")
      (node (ref "SW2") (pin "P4") (pinfunction "NC1_P4") (pintype "bidirectional"))
    )
    (net (code "108") (name "unconnected-(SW2-NO1-PadP5)") (class "Default")
      (node (ref "SW2") (pin "P5") (pinfunction "NO1_P5") (pintype "bidirectional"))
    )
  )
)
